# PLD_FRAM-Memory.net
KiCad netlist of a schematic drawn in Altium Designer
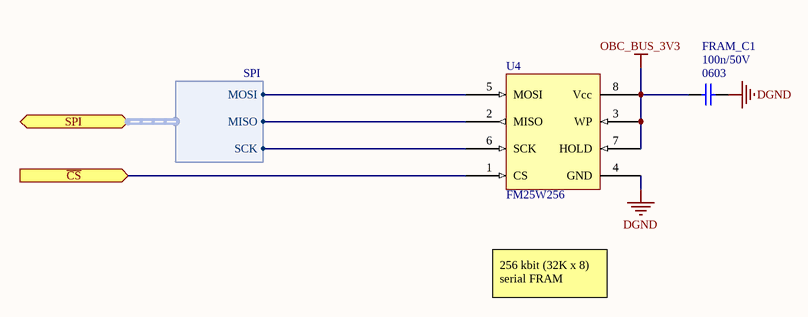
[diagram p0: PLD_FRAM-Memory.SchDoc]

(export (version "E")
  (design (tool "Eeschema 10.0.6"))
  (components
    (comp (ref "FRAM_C1")
      (value "100n/50V")
      (footprint "SMD_Capacitor_0603")
      (description "Ceramic Cap Kemet COTS 100n/50V X7R 0603")
      (fields
        (field (name "MANUFACTURER") "Kemet")
        (field (name "MANUFACTURERPARTNUMBER") "C0603T104K5RALTU")
        (field (name "PACKAGE") "0603")
      )
      (libsource (lib "capacitors") (part "Cer_C0603T104K5RALTU"))
    )
    (comp (ref "U4")
      (value "FM25W256")
      (footprint "SOIC-8-N")
      (description "256Kb (8k x 32) SPI F-RAM")
      (libsource (lib "microcircuits") (part "FM25W256"))
    )
  )
  (nets
    (net (code "2") (name "/MISO") (class "Default")
      (node (ref "U4") (pin "2") (pinfunction "MISO_2") (pintype "output"))
    )
    (net (code "3") (name "/MOSI") (class "Default")
      (node (ref "U4") (pin "5") (pinfunction "MOSI_5") (pintype "input"))
    )
    (net (code "4") (name "/SCK") (class "Default")
      (node (ref "U4") (pin "6") (pinfunction "SCK_6") (pintype "input"))
    )
    (net (code "6") (name "/~{CS}") (class "Default")
      (node (ref "U4") (pin "1") (pinfunction "CS_1") (pintype "input"))
    )
    (net (code "7") (name "DGND") (class "Default")
      (node (ref "FRAM_C1") (pin "1") (pinfunction "1_1") (pintype "passive"))
      (node (ref "U4") (pin "4") (pinfunction "GND_4") (pintype "power_in"))
    )
    (net (code "8") (name "OBC_BUS_3V3") (class "Default")
      (node (ref "FRAM_C1") (pin "2") (pinfunction "2_2") (pintype "passive"))
      (node (ref "U4") (pin "3") (pinfunction "WP_3") (pintype "input"))
      (node (ref "U4") (pin "7") (pinfunction "HOLD_7") (pintype "input"))
      (node (ref "U4") (pin "8") (pinfunction "Vcc_8") (pintype "power_in"))
    )
  )
)
